# followLineSensor.net
KiCad netlist of a schematic drawn in EAGLE
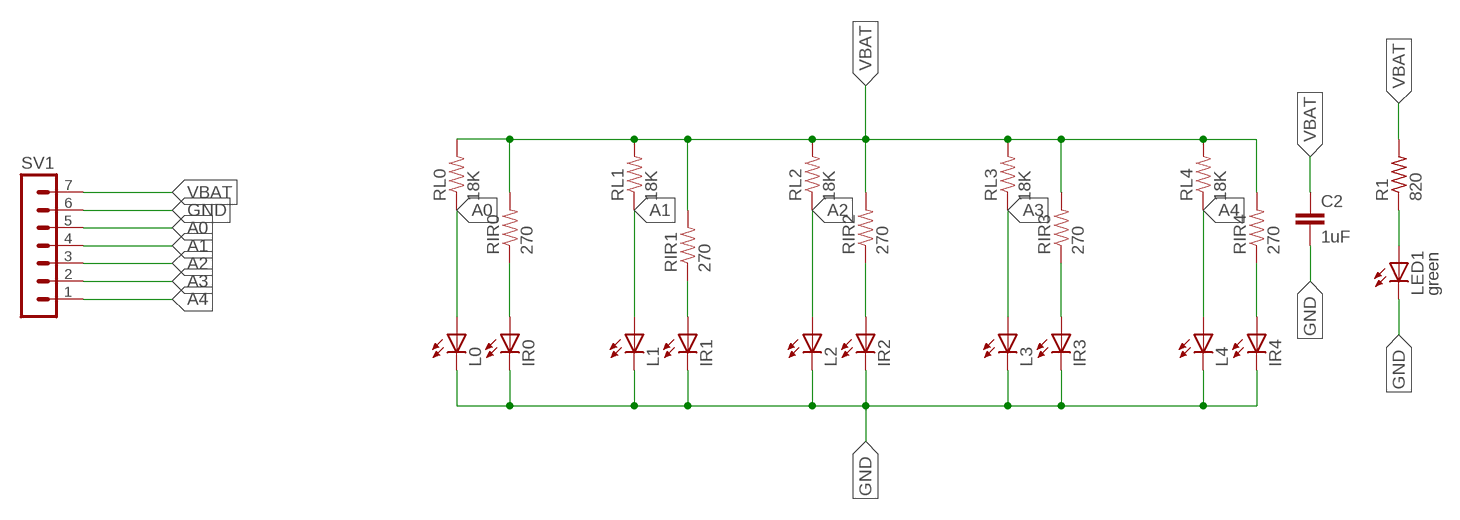
[diagram p0: schematic, sheet 1]

(export (version "E")
  (design (tool "Eeschema 10.0.6"))
  (components
    (comp (ref "C2")
      (value "1uF")
      (footprint "eagle-import:C1206")
      (libsource (lib "eagle-import") (part "C-EUC1206"))
    )
    (comp (ref "IR0")
      (value "LED5MM")
      (footprint "eagle-import:LED5MM")
      (libsource (lib "eagle-import") (part "LED5MM"))
    )
    (comp (ref "IR1")
      (value "LED5MM")
      (footprint "eagle-import:LED5MM")
      (libsource (lib "eagle-import") (part "LED5MM"))
    )
    (comp (ref "IR2")
      (value "LED5MM")
      (footprint "eagle-import:LED5MM")
      (libsource (lib "eagle-import") (part "LED5MM"))
    )
    (comp (ref "IR3")
      (value "LED5MM")
      (footprint "eagle-import:LED5MM")
      (libsource (lib "eagle-import") (part "LED5MM"))
    )
    (comp (ref "IR4")
      (value "LED5MM")
      (footprint "eagle-import:LED5MM")
      (libsource (lib "eagle-import") (part "LED5MM"))
    )
    (comp (ref "L0")
      (value "LED5MM")
      (footprint "eagle-import:LED5MM")
      (libsource (lib "eagle-import") (part "LED5MM"))
    )
    (comp (ref "L1")
      (value "LED5MM")
      (footprint "eagle-import:LED5MM")
      (libsource (lib "eagle-import") (part "LED5MM"))
    )
    (comp (ref "L2")
      (value "LED5MM")
      (footprint "eagle-import:LED5MM")
      (libsource (lib "eagle-import") (part "LED5MM"))
    )
    (comp (ref "L3")
      (value "LED5MM")
      (footprint "eagle-import:LED5MM")
      (libsource (lib "eagle-import") (part "LED5MM"))
    )
    (comp (ref "L4")
      (value "LED5MM")
      (footprint "eagle-import:LED5MM")
      (libsource (lib "eagle-import") (part "LED5MM"))
    )
    (comp (ref "LED1")
      (value "green")
      (footprint "eagle-import:SML0805")
      (libsource (lib "eagle-import") (part "LEDSML0805"))
    )
    (comp (ref "R1")
      (value "820")
      (footprint "eagle-import:R0805")
      (libsource (lib "eagle-import") (part "R-US_R0805"))
    )
    (comp (ref "RIR0")
      (value "270")
      (footprint "eagle-import:1206")
      (libsource (lib "eagle-import") (part "RESISTOR1206"))
    )
    (comp (ref "RIR1")
      (value "270")
      (footprint "eagle-import:1206")
      (libsource (lib "eagle-import") (part "RESISTOR1206"))
    )
    (comp (ref "RIR2")
      (value "270")
      (footprint "eagle-import:1206")
      (libsource (lib "eagle-import") (part "RESISTOR1206"))
    )
    (comp (ref "RIR3")
      (value "270")
      (footprint "eagle-import:1206")
      (libsource (lib "eagle-import") (part "RESISTOR1206"))
    )
    (comp (ref "RIR4")
      (value "270")
      (footprint "eagle-import:1206")
      (libsource (lib "eagle-import") (part "RESISTOR1206"))
    )
    (comp (ref "RL0")
      (value "18K")
      (footprint "eagle-import:1206")
      (libsource (lib "eagle-import") (part "RESISTOR1206"))
    )
    (comp (ref "RL1")
      (value "18K")
      (footprint "eagle-import:1206")
      (libsource (lib "eagle-import") (part "RESISTOR1206"))
    )
    (comp (ref "RL2")
      (value "18K")
      (footprint "eagle-import:1206")
      (libsource (lib "eagle-import") (part "RESISTOR1206"))
    )
    (comp (ref "RL3")
      (value "18K")
      (footprint "eagle-import:1206")
      (libsource (lib "eagle-import") (part "RESISTOR1206"))
    )
    (comp (ref "RL4")
      (value "18K")
      (footprint "eagle-import:1206")
      (libsource (lib "eagle-import") (part "RESISTOR1206"))
    )
    (comp (ref "SV1")
      (value "MA07-1")
      (footprint "eagle-import:MA07-1")
      (libsource (lib "eagle-import") (part "MA07-1"))
    )
  )
  (nets
    (net (code "1") (name "A0") (class "Default")
      (node (ref "L0") (pin "A") (pinfunction "A_A") (pintype "passive"))
      (node (ref "RL0") (pin "1") (pinfunction "1_1") (pintype "passive"))
      (node (ref "SV1") (pin "5") (pinfunction "5_5") (pintype "passive"))
    )
    (net (code "2") (name "A1") (class "Default")
      (node (ref "L1") (pin "A") (pinfunction "A_A") (pintype "passive"))
      (node (ref "RL1") (pin "1") (pinfunction "1_1") (pintype "passive"))
      (node (ref "SV1") (pin "4") (pinfunction "4_4") (pintype "passive"))
    )
    (net (code "3") (name "A2") (class "Default")
      (node (ref "L2") (pin "A") (pinfunction "A_A") (pintype "passive"))
      (node (ref "RL2") (pin "1") (pinfunction "1_1") (pintype "passive"))
      (node (ref "SV1") (pin "3") (pinfunction "3_3") (pintype "passive"))
    )
    (net (code "4") (name "A3") (class "Default")
      (node (ref "L3") (pin "A") (pinfunction "A_A") (pintype "passive"))
      (node (ref "RL3") (pin "1") (pinfunction "1_1") (pintype "passive"))
      (node (ref "SV1") (pin "2") (pinfunction "2_2") (pintype "passive"))
    )
    (net (code "5") (name "A4") (class "Default")
      (node (ref "L4") (pin "A") (pinfunction "A_A") (pintype "passive"))
      (node (ref "RL4") (pin "1") (pinfunction "1_1") (pintype "passive"))
      (node (ref "SV1") (pin "1") (pinfunction "1_1") (pintype "passive"))
    )
    (net (code "6") (name "GND") (class "Default")
      (node (ref "C2") (pin "2") (pinfunction "2_2") (pintype "passive"))
      (node (ref "IR0") (pin "K") (pinfunction "C_K") (pintype "passive"))
      (node (ref "IR1") (pin "K") (pinfunction "C_K") (pintype "passive"))
      (node (ref "IR2") (pin "K") (pinfunction "C_K") (pintype "passive"))
      (node (ref "IR3") (pin "K") (pinfunction "C_K") (pintype "passive"))
      (node (ref "IR4") (pin "K") (pinfunction "C_K") (pintype "passive"))
      (node (ref "L0") (pin "K") (pinfunction "C_K") (pintype "passive"))
      (node (ref "L1") (pin "K") (pinfunction "C_K") (pintype "passive"))
      (node (ref "L2") (pin "K") (pinfunction "C_K") (pintype "passive"))
      (node (ref "L3") (pin "K") (pinfunction "C_K") (pintype "passive"))
      (node (ref "L4") (pin "K") (pinfunction "C_K") (pintype "passive"))
      (node (ref "LED1") (pin "C") (pinfunction "C_C") (pintype "passive"))
      (node (ref "SV1") (pin "6") (pinfunction "6_6") (pintype "passive"))
    )
    (net (code "7") (name "Net-(IR0-PadA)") (class "Default")
      (node (ref "IR0") (pin "A") (pinfunction "A_A") (pintype "passive"))
      (node (ref "RIR0") (pin "1") (pinfunction "1_1") (pintype "passive"))
    )
    (net (code "8") (name "Net-(IR1-PadA)") (class "Default")
      (node (ref "IR1") (pin "A") (pinfunction "A_A") (pintype "passive"))
      (node (ref "RIR1") (pin "1") (pinfunction "1_1") (pintype "passive"))
    )
    (net (code "9") (name "Net-(IR2-PadA)") (class "Default")
      (node (ref "IR2") (pin "A") (pinfunction "A_A") (pintype "passive"))
      (node (ref "RIR2") (pin "1") (pinfunction "1_1") (pintype "passive"))
    )
    (net (code "10") (name "Net-(IR3-PadA)") (class "Default")
      (node (ref "IR3") (pin "A") (pinfunction "A_A") (pintype "passive"))
      (node (ref "RIR3") (pin "1") (pinfunction "1_1") (pintype "passive"))
    )
    (net (code "11") (name "Net-(IR4-PadA)") (class "Default")
      (node (ref "IR4") (pin "A") (pinfunction "A_A") (pintype "passive"))
      (node (ref "RIR4") (pin "1") (pinfunction "1_1") (pintype "passive"))
    )
    (net (code "12") (name "Net-(LED1-PadA)") (class "Default")
      (node (ref "LED1") (pin "A") (pinfunction "A_A") (pintype "passive"))
      (node (ref "R1") (pin "1") (pinfunction "1_1") (pintype "passive"))
    )
    (net (code "13") (name "VBAT") (class "Default")
      (node (ref "C2") (pin "1") (pinfunction "1_1") (pintype "passive"))
      (node (ref "R1") (pin "2") (pinfunction "2_2") (pintype "passive"))
      (node (ref "RIR0") (pin "2") (pinfunction "2_2") (pintype "passive"))
      (node (ref "RIR1") (pin "2") (pinfunction "2_2") (pintype "passive"))
      (node (ref "RIR2") (pin "2") (pinfunction "2_2") (pintype "passive"))
      (node (ref "RIR3") (pin "2") (pinfunction "2_2") (pintype "passive"))
      (node (ref "RIR4") (pin "2") (pinfunction "2_2") (pintype "passive"))
      (node (ref "RL0") (pin "2") (pinfunction "2_2") (pintype "passive"))
      (node (ref "RL1") (pin "2") (pinfunction "2_2") (pintype "passive"))
      (node (ref "RL2") (pin "2") (pinfunction "2_2") (pintype "passive"))
      (node (ref "RL3") (pin "2") (pinfunction "2_2") (pintype "passive"))
      (node (ref "RL4") (pin "2") (pinfunction "2_2") (pintype "passive"))
      (node (ref "SV1") (pin "7") (pinfunction "7_7") (pintype "passive"))
    )
  )
)
